# buffered_leds.net
KiCad netlist of a schematic drawn in Altium Designer
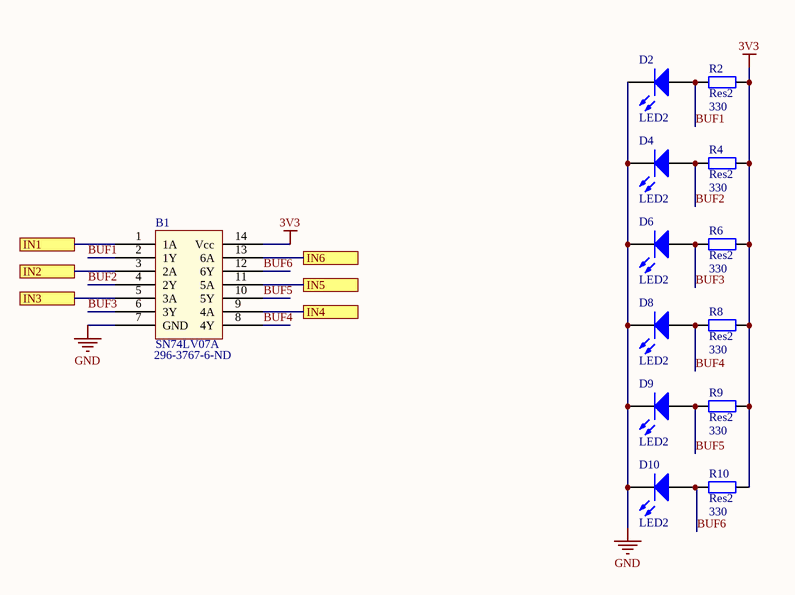
[diagram p0: buffered_leds.SchDoc]

(export (version "E")
  (design (tool "Eeschema 10.0.6"))
  (components
    (comp (ref "B1")
      (value "SN74LV07A")
      (footprint "SOIC127P600X175-14N")
      (fields (field (name "SUPPLIER PART NUMBER 1") "296-3767-6-ND"))
      (libsource (lib "SN74LV07ADR") (part "SN74LV07A"))
    )
    (comp (ref "D2")
      (value "LED2")
      (footprint "0603-LED")
      (description "Typical RED, GREEN, YELLOW, AMBER GaAs LED")
      (fields (field (name "PUBLISHER") "Altium Limited"))
      (libsource (lib "Miscellaneous Devices") (part "LED2"))
    )
    (comp (ref "D4")
      (value "LED2")
      (footprint "0603-LED")
      (description "Typical RED, GREEN, YELLOW, AMBER GaAs LED")
      (fields (field (name "PUBLISHER") "Altium Limited"))
      (libsource (lib "Miscellaneous Devices") (part "LED2"))
    )
    (comp (ref "D6")
      (value "LED2")
      (footprint "0603-LED")
      (description "Typical RED, GREEN, YELLOW, AMBER GaAs LED")
      (fields (field (name "PUBLISHER") "Altium Limited"))
      (libsource (lib "Miscellaneous Devices") (part "LED2"))
    )
    (comp (ref "D8")
      (value "LED2")
      (footprint "0603-LED")
      (description "Typical RED, GREEN, YELLOW, AMBER GaAs LED")
      (fields (field (name "PUBLISHER") "Altium Limited"))
      (libsource (lib "Miscellaneous Devices") (part "LED2"))
    )
    (comp (ref "D9")
      (value "LED2")
      (footprint "0603-LED")
      (description "Typical RED, GREEN, YELLOW, AMBER GaAs LED")
      (fields (field (name "PUBLISHER") "Altium Limited"))
      (libsource (lib "Miscellaneous Devices") (part "LED2"))
    )
    (comp (ref "D10")
      (value "LED2")
      (footprint "0603-LED")
      (description "Typical RED, GREEN, YELLOW, AMBER GaAs LED")
      (fields (field (name "PUBLISHER") "Altium Limited"))
      (libsource (lib "Miscellaneous Devices") (part "LED2"))
    )
    (comp (ref "R2")
      (value "Res2")
      (footprint "J1-0603")
      (description "Resistor")
      (fields (field (name "ALTIUM_VALUE") "330") (field (name "PUBLISHER") "Altium Limited"))
      (libsource (lib "Miscellaneous Devices") (part "Res2"))
    )
    (comp (ref "R4")
      (value "Res2")
      (footprint "J1-0603")
      (description "Resistor")
      (fields (field (name "ALTIUM_VALUE") "330") (field (name "PUBLISHER") "Altium Limited"))
      (libsource (lib "Miscellaneous Devices") (part "Res2"))
    )
    (comp (ref "R6")
      (value "Res2")
      (footprint "J1-0603")
      (description "Resistor")
      (fields (field (name "ALTIUM_VALUE") "330") (field (name "PUBLISHER") "Altium Limited"))
      (libsource (lib "Miscellaneous Devices") (part "Res2"))
    )
    (comp (ref "R8")
      (value "Res2")
      (footprint "J1-0603")
      (description "Resistor")
      (fields (field (name "ALTIUM_VALUE") "330") (field (name "PUBLISHER") "Altium Limited"))
      (libsource (lib "Miscellaneous Devices") (part "Res2"))
    )
    (comp (ref "R9")
      (value "Res2")
      (footprint "J1-0603")
      (description "Resistor")
      (fields (field (name "ALTIUM_VALUE") "330") (field (name "PUBLISHER") "Altium Limited"))
      (libsource (lib "Miscellaneous Devices") (part "Res2"))
    )
    (comp (ref "R10")
      (value "Res2")
      (footprint "J1-0603")
      (description "Resistor")
      (fields (field (name "ALTIUM_VALUE") "330") (field (name "PUBLISHER") "Altium Limited"))
      (libsource (lib "Miscellaneous Devices") (part "Res2"))
    )
  )
  (nets
    (net (code "1") (name "/BUF1") (class "Default")
      (node (ref "B1") (pin "2") (pinfunction "1Y_2") (pintype "passive"))
      (node (ref "D2") (pin "1") (pinfunction "A_1") (pintype "passive"))
      (node (ref "R2") (pin "2") (pinfunction "2_2") (pintype "passive"))
    )
    (net (code "2") (name "/BUF2") (class "Default")
      (node (ref "B1") (pin "4") (pinfunction "2Y_4") (pintype "passive"))
      (node (ref "D4") (pin "1") (pinfunction "A_1") (pintype "passive"))
      (node (ref "R4") (pin "2") (pinfunction "2_2") (pintype "passive"))
    )
    (net (code "3") (name "/BUF3") (class "Default")
      (node (ref "B1") (pin "6") (pinfunction "3Y_6") (pintype "passive"))
      (node (ref "D6") (pin "1") (pinfunction "A_1") (pintype "passive"))
      (node (ref "R6") (pin "2") (pinfunction "2_2") (pintype "passive"))
    )
    (net (code "4") (name "/BUF4") (class "Default")
      (node (ref "B1") (pin "8") (pinfunction "4Y_8") (pintype "passive"))
      (node (ref "D8") (pin "1") (pinfunction "A_1") (pintype "passive"))
      (node (ref "R8") (pin "2") (pinfunction "2_2") (pintype "passive"))
    )
    (net (code "5") (name "/BUF5") (class "Default")
      (node (ref "B1") (pin "10") (pinfunction "5Y_10") (pintype "passive"))
      (node (ref "D9") (pin "1") (pinfunction "A_1") (pintype "passive"))
      (node (ref "R9") (pin "2") (pinfunction "2_2") (pintype "passive"))
    )
    (net (code "6") (name "/BUF6") (class "Default")
      (node (ref "B1") (pin "12") (pinfunction "6Y_12") (pintype "passive"))
      (node (ref "D10") (pin "1") (pinfunction "A_1") (pintype "passive"))
      (node (ref "R10") (pin "2") (pinfunction "2_2") (pintype "passive"))
    )
    (net (code "7") (name "/IN1") (class "Default")
      (node (ref "B1") (pin "1") (pinfunction "1A_1") (pintype "passive"))
    )
    (net (code "8") (name "/IN2") (class "Default")
      (node (ref "B1") (pin "3") (pinfunction "2A_3") (pintype "passive"))
    )
    (net (code "9") (name "/IN3") (class "Default")
      (node (ref "B1") (pin "5") (pinfunction "3A_5") (pintype "passive"))
    )
    (net (code "10") (name "/IN4") (class "Default")
      (node (ref "B1") (pin "9") (pinfunction "4A_9") (pintype "passive"))
    )
    (net (code "11") (name "/IN5") (class "Default")
      (node (ref "B1") (pin "11") (pinfunction "5A_11") (pintype "passive"))
    )
    (net (code "12") (name "/IN6") (class "Default")
      (node (ref "B1") (pin "13") (pinfunction "6A_13") (pintype "passive"))
    )
    (net (code "13") (name "3V3") (class "Default")
      (node (ref "B1") (pin "14") (pinfunction "Vcc_14") (pintype "passive"))
      (node (ref "R10") (pin "1") (pinfunction "1_1") (pintype "passive"))
      (node (ref "R2") (pin "1") (pinfunction "1_1") (pintype "passive"))
      (node (ref "R4") (pin "1") (pinfunction "1_1") (pintype "passive"))
      (node (ref "R6") (pin "1") (pinfunction "1_1") (pintype "passive"))
      (node (ref "R8") (pin "1") (pinfunction "1_1") (pintype "passive"))
      (node (ref "R9") (pin "1") (pinfunction "1_1") (pintype "passive"))
    )
    (net (code "14") (name "GND") (class "Default")
      (node (ref "B1") (pin "7") (pinfunction "GND_7") (pintype "power_in"))
      (node (ref "D10") (pin "2") (pinfunction "K_2") (pintype "passive"))
      (node (ref "D2") (pin "2") (pinfunction "K_2") (pintype "passive"))
      (node (ref "D4") (pin "2") (pinfunction "K_2") (pintype "passive"))
      (node (ref "D6") (pin "2") (pinfunction "K_2") (pintype "passive"))
      (node (ref "D8") (pin "2") (pinfunction "K_2") (pintype "passive"))
      (node (ref "D9") (pin "2") (pinfunction "K_2") (pintype "passive"))
    )
  )
)
